# MO-bela-lightspace-A.net
KiCad netlist of a schematic drawn in EAGLE
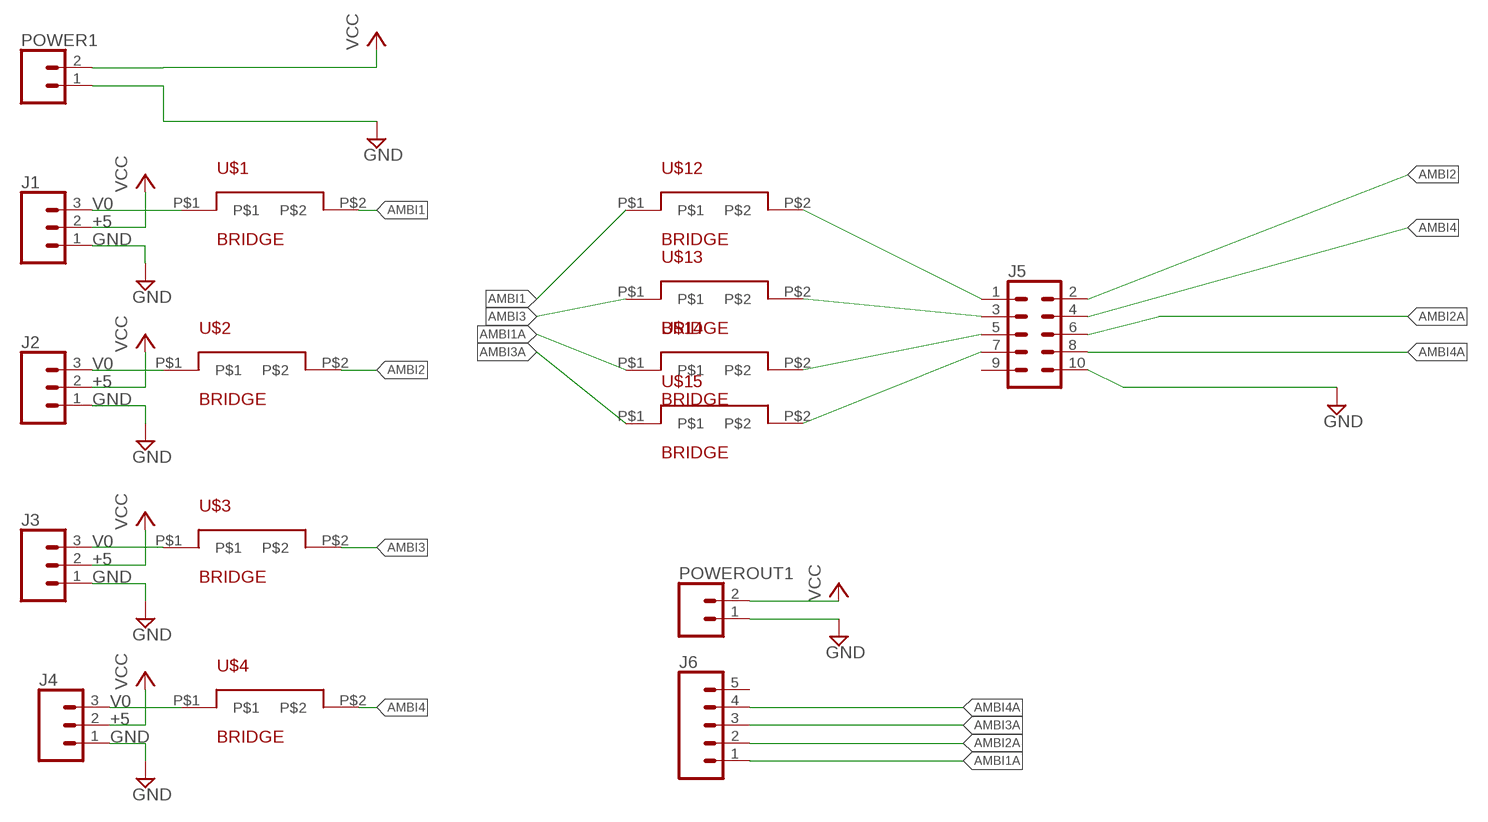
[diagram p0: schematic, sheet 1]

(export (version "E")
  (design (tool "Eeschema 10.0.6"))
  (components
    (comp (ref "J1")
      (value "CONN_03LOCK")
      (footprint "eagle-import:1X03_LOCK")
      (fields (field (name "5") "+5"))
      (libsource (lib "eagle-import") (part "CONN_03LOCK"))
    )
    (comp (ref "J2")
      (value "CONN_03LOCK")
      (footprint "eagle-import:1X03_LOCK")
      (fields (field (name "5") "+5"))
      (libsource (lib "eagle-import") (part "CONN_03LOCK"))
    )
    (comp (ref "J3")
      (value "CONN_03LOCK")
      (footprint "eagle-import:1X03_LOCK")
      (fields (field (name "5") "+5"))
      (libsource (lib "eagle-import") (part "CONN_03LOCK"))
    )
    (comp (ref "J4")
      (value "CONN_03LOCK")
      (footprint "eagle-import:1X03_LOCK")
      (fields (field (name "5") "+5"))
      (libsource (lib "eagle-import") (part "CONN_03LOCK"))
    )
    (comp (ref "J5")
      (value "CONN_05X2SHD_LOCK")
      (footprint "eagle-import:2X5-SHROUDED_LOCK")
      (libsource (lib "eagle-import") (part "CONN_05X2SHD_LOCK"))
    )
    (comp (ref "J6")
      (value "CONN_05LOCK")
      (footprint "eagle-import:1X05_LOCK")
      (libsource (lib "eagle-import") (part "CONN_05LOCK"))
    )
    (comp (ref "POWER1")
      (value "CONN_02LOCK")
      (footprint "eagle-import:1X02_LOCK")
      (libsource (lib "eagle-import") (part "CONN_02LOCK"))
    )
    (comp (ref "POWEROUT1")
      (value "CONN_02LOCK")
      (footprint "eagle-import:1X02_LOCK")
      (libsource (lib "eagle-import") (part "CONN_02LOCK"))
    )
    (comp (ref "U$1")
      (value "BRIDGE")
      (footprint "eagle-import:BRIDGE")
      (libsource (lib "eagle-import") (part "BRIDGE"))
    )
    (comp (ref "U$2")
      (value "BRIDGE")
      (footprint "eagle-import:BRIDGE")
      (libsource (lib "eagle-import") (part "BRIDGE"))
    )
    (comp (ref "U$3")
      (value "BRIDGE")
      (footprint "eagle-import:BRIDGE")
      (libsource (lib "eagle-import") (part "BRIDGE"))
    )
    (comp (ref "U$4")
      (value "BRIDGE")
      (footprint "eagle-import:BRIDGE")
      (libsource (lib "eagle-import") (part "BRIDGE"))
    )
    (comp (ref "U$12")
      (value "BRIDGE")
      (footprint "eagle-import:BRIDGE")
      (libsource (lib "eagle-import") (part "BRIDGE"))
    )
    (comp (ref "U$13")
      (value "BRIDGE")
      (footprint "eagle-import:BRIDGE")
      (libsource (lib "eagle-import") (part "BRIDGE"))
    )
    (comp (ref "U$14")
      (value "BRIDGE")
      (footprint "eagle-import:BRIDGE")
      (libsource (lib "eagle-import") (part "BRIDGE"))
    )
    (comp (ref "U$15")
      (value "BRIDGE")
      (footprint "eagle-import:BRIDGE")
      (libsource (lib "eagle-import") (part "BRIDGE"))
    )
  )
  (nets
    (net (code "1") (name "AMBI1") (class "Default")
      (node (ref "U$1") (pin "P$2") (pinfunction "P$2_P$2") (pintype "bidirectional"))
      (node (ref "U$12") (pin "P$1") (pinfunction "P$1_P$1") (pintype "bidirectional"))
    )
    (net (code "2") (name "AMBI1A") (class "Default")
      (node (ref "J6") (pin "1") (pinfunction "1_1") (pintype "passive"))
      (node (ref "U$14") (pin "P$1") (pinfunction "P$1_P$1") (pintype "bidirectional"))
    )
    (net (code "3") (name "AMBI2") (class "Default")
      (node (ref "J5") (pin "2") (pinfunction "2_2") (pintype "passive"))
      (node (ref "U$2") (pin "P$2") (pinfunction "P$2_P$2") (pintype "bidirectional"))
    )
    (net (code "4") (name "AMBI2A") (class "Default")
      (node (ref "J5") (pin "6") (pinfunction "6_6") (pintype "passive"))
      (node (ref "J6") (pin "2") (pinfunction "2_2") (pintype "passive"))
    )
    (net (code "5") (name "AMBI3") (class "Default")
      (node (ref "U$13") (pin "P$1") (pinfunction "P$1_P$1") (pintype "bidirectional"))
      (node (ref "U$3") (pin "P$2") (pinfunction "P$2_P$2") (pintype "bidirectional"))
    )
    (net (code "6") (name "AMBI3A") (class "Default")
      (node (ref "J6") (pin "3") (pinfunction "3_3") (pintype "passive"))
      (node (ref "U$15") (pin "P$1") (pinfunction "P$1_P$1") (pintype "bidirectional"))
    )
    (net (code "7") (name "AMBI4") (class "Default")
      (node (ref "J5") (pin "4") (pinfunction "4_4") (pintype "passive"))
      (node (ref "U$4") (pin "P$2") (pinfunction "P$2_P$2") (pintype "bidirectional"))
    )
    (net (code "8") (name "AMBI4A") (class "Default")
      (node (ref "J5") (pin "8") (pinfunction "8_8") (pintype "passive"))
      (node (ref "J6") (pin "4") (pinfunction "4_4") (pintype "passive"))
    )
    (net (code "9") (name "GND") (class "Default")
      (node (ref "J1") (pin "1") (pinfunction "1_1") (pintype "passive"))
      (node (ref "J2") (pin "1") (pinfunction "1_1") (pintype "passive"))
      (node (ref "J3") (pin "1") (pinfunction "1_1") (pintype "passive"))
      (node (ref "J4") (pin "1") (pinfunction "1_1") (pintype "passive"))
      (node (ref "J5") (pin "10") (pinfunction "10_10") (pintype "passive"))
      (node (ref "POWER1") (pin "1") (pinfunction "1_1") (pintype "passive"))
      (node (ref "POWEROUT1") (pin "1") (pinfunction "1_1") (pintype "passive"))
    )
    (net (code "10") (name "Net-(J1-Pad3)") (class "Default")
      (node (ref "J1") (pin "3") (pinfunction "3_3") (pintype "passive"))
      (node (ref "U$1") (pin "P$1") (pinfunction "P$1_P$1") (pintype "bidirectional"))
    )
    (net (code "11") (name "Net-(J2-Pad3)") (class "Default")
      (node (ref "J2") (pin "3") (pinfunction "3_3") (pintype "passive"))
      (node (ref "U$2") (pin "P$1") (pinfunction "P$1_P$1") (pintype "bidirectional"))
    )
    (net (code "12") (name "Net-(J3-Pad3)") (class "Default")
      (node (ref "J3") (pin "3") (pinfunction "3_3") (pintype "passive"))
      (node (ref "U$3") (pin "P$1") (pinfunction "P$1_P$1") (pintype "bidirectional"))
    )
    (net (code "13") (name "Net-(J4-Pad3)") (class "Default")
      (node (ref "J4") (pin "3") (pinfunction "3_3") (pintype "passive"))
      (node (ref "U$4") (pin "P$1") (pinfunction "P$1_P$1") (pintype "bidirectional"))
    )
    (net (code "14") (name "Net-(J5-Pad1)") (class "Default")
      (node (ref "J5") (pin "1") (pinfunction "1_1") (pintype "passive"))
      (node (ref "U$12") (pin "P$2") (pinfunction "P$2_P$2") (pintype "bidirectional"))
    )
    (net (code "15") (name "Net-(J5-Pad3)") (class "Default")
      (node (ref "J5") (pin "3") (pinfunction "3_3") (pintype "passive"))
      (node (ref "U$13") (pin "P$2") (pinfunction "P$2_P$2") (pintype "bidirectional"))
    )
    (net (code "16") (name "Net-(J5-Pad5)") (class "Default")
      (node (ref "J5") (pin "5") (pinfunction "5_5") (pintype "passive"))
      (node (ref "U$14") (pin "P$2") (pinfunction "P$2_P$2") (pintype "bidirectional"))
    )
    (net (code "17") (name "Net-(J5-Pad7)") (class "Default")
      (node (ref "J5") (pin "7") (pinfunction "7_7") (pintype "passive"))
      (node (ref "U$15") (pin "P$2") (pinfunction "P$2_P$2") (pintype "bidirectional"))
    )
    (net (code "18") (name "VCC") (class "Default")
      (node (ref "J1") (pin "2") (pinfunction "2_2") (pintype "passive"))
      (node (ref "J2") (pin "2") (pinfunction "2_2") (pintype "passive"))
      (node (ref "J3") (pin "2") (pinfunction "2_2") (pintype "passive"))
      (node (ref "J4") (pin "2") (pinfunction "2_2") (pintype "passive"))
      (node (ref "POWER1") (pin "2") (pinfunction "2_2") (pintype "passive"))
      (node (ref "POWEROUT1") (pin "2") (pinfunction "2_2") (pintype "passive"))
    )
    (net (code "19") (name "unconnected-(J5-Pad9)") (class "Default")
      (node (ref "J5") (pin "9") (pinfunction "9_9") (pintype "passive"))
    )
    (net (code "20") (name "unconnected-(J6-Pad5)") (class "Default")
      (node (ref "J6") (pin "5") (pinfunction "5_5") (pintype "passive"))
    )
  )
)
